# VideoSignal.net
KiCad netlist of a schematic drawn in Altium Designer
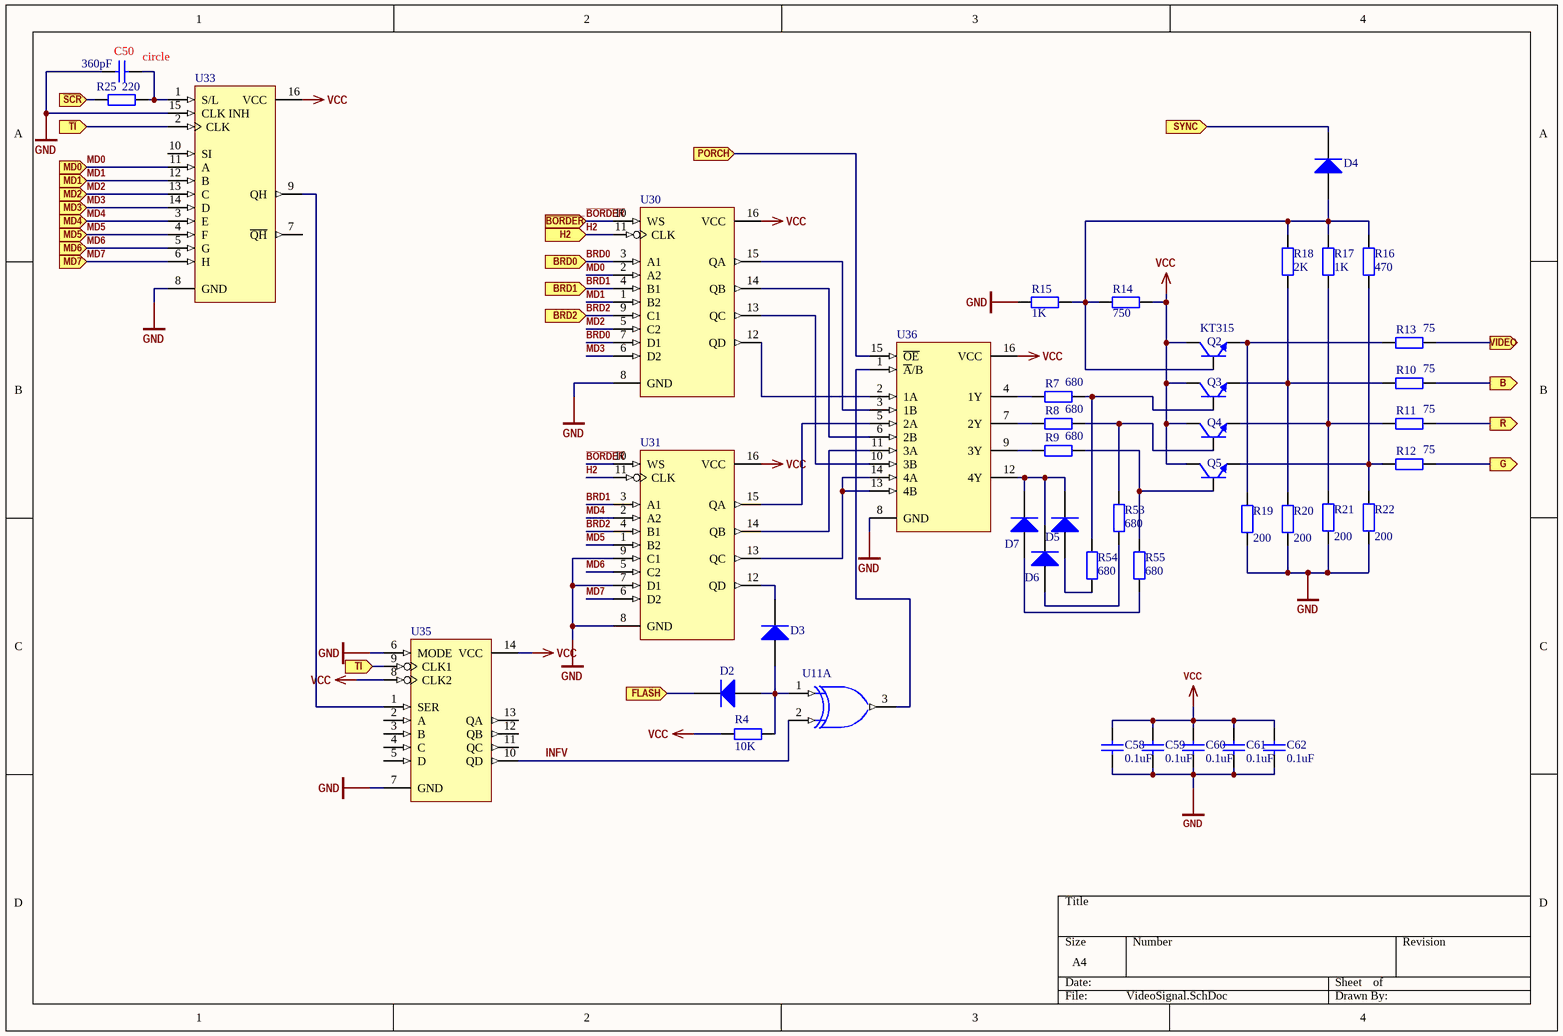
[diagram p0: VideoSignal.SchDoc]

(export (version "E")
  (design (tool "Eeschema 10.0.6"))
  (components
    (comp (ref "C50")
      (value "circle")
      (footprint "RAD-0.3")
      (description "Capacitor")
      (fields (field (name "ALTIUM_VALUE") "360pF") (field (name "PUBLISHER") "Altium Limited"))
      (libsource (lib "Lenin") (part "Cap"))
    )
    (comp (ref "C58")
      (value "0.1uF")
      (footprint "RAD-0.3")
      (description "Capacitor")
      (fields (field (name "Comment") "Cap") (field (name "PUBLISHER") "Altium Limited"))
      (libsource (lib "Lenin") (part "Cap"))
    )
    (comp (ref "C59")
      (value "0.1uF")
      (footprint "RAD-0.3")
      (description "Capacitor")
      (fields (field (name "Comment") "Cap") (field (name "PUBLISHER") "Altium Limited"))
      (libsource (lib "Lenin") (part "Cap"))
    )
    (comp (ref "C60")
      (value "0.1uF")
      (footprint "RAD-0.3")
      (description "Capacitor")
      (fields (field (name "Comment") "Cap") (field (name "PUBLISHER") "Altium Limited"))
      (libsource (lib "Lenin") (part "Cap"))
    )
    (comp (ref "C61")
      (value "0.1uF")
      (footprint "RAD-0.3")
      (description "Capacitor")
      (fields (field (name "Comment") "Cap") (field (name "PUBLISHER") "Altium Limited"))
      (libsource (lib "Lenin") (part "Cap"))
    )
    (comp (ref "C62")
      (value "0.1uF")
      (footprint "RAD-0.3")
      (description "Capacitor")
      (fields (field (name "Comment") "Cap") (field (name "PUBLISHER") "Altium Limited"))
      (libsource (lib "Lenin") (part "Cap"))
    )
    (comp (ref "D2")
      (value "~")
      (footprint "DO-35A")
      (description "Computer Diode")
      (fields (field (name "PUBLISHER") "Altium Limited"))
      (libsource (lib "Miscellaneous Devices") (part "Diode 1N4149"))
    )
    (comp (ref "D3")
      (value "~")
      (footprint "DO-35A")
      (description "Computer Diode")
      (fields (field (name "PUBLISHER") "Altium Limited"))
      (libsource (lib "Miscellaneous Devices") (part "Diode 1N4149"))
    )
    (comp (ref "D4")
      (value "Diode 1N4148")
      (footprint "DO-35")
      (description "High Conductance Fast Diode")
      (fields (field (name "PUBLISHER") "Altium Limited"))
      (libsource (lib "Miscellaneous Devices") (part "Diode 1N4148"))
    )
    (comp (ref "D5")
      (value "Diode 1N4148")
      (footprint "DO-35")
      (description "High Conductance Fast Diode")
      (fields (field (name "PUBLISHER") "Altium Limited"))
      (libsource (lib "Miscellaneous Devices") (part "Diode 1N4148"))
    )
    (comp (ref "D6")
      (value "Diode 1N4148")
      (footprint "DO-35")
      (description "High Conductance Fast Diode")
      (fields (field (name "PUBLISHER") "Altium Limited"))
      (libsource (lib "Miscellaneous Devices") (part "Diode 1N4148"))
    )
    (comp (ref "D7")
      (value "Diode 1N4148")
      (footprint "DO-35")
      (description "High Conductance Fast Diode")
      (fields (field (name "PUBLISHER") "Altium Limited"))
      (libsource (lib "Miscellaneous Devices") (part "Diode 1N4148"))
    )
    (comp (ref "Q2")
      (value "KT315")
      (footprint "Lenin:D35")
      (description "NPN General Purpose Amplifier")
      (fields (field (name "PUBLISHER") "Altium Limited"))
      (libsource (lib "Lenin") (part "KT315"))
    )
    (comp (ref "Q3")
      (value "KT315")
      (footprint "Lenin:D35")
      (description "NPN General Purpose Amplifier")
      (fields (field (name "PUBLISHER") "Altium Limited"))
      (libsource (lib "Lenin") (part "KT315"))
    )
    (comp (ref "Q4")
      (value "KT315")
      (footprint "Lenin:D35")
      (description "NPN General Purpose Amplifier")
      (fields (field (name "PUBLISHER") "Altium Limited"))
      (libsource (lib "Lenin") (part "KT315"))
    )
    (comp (ref "Q5")
      (value "KT315")
      (footprint "Lenin:D35")
      (description "NPN General Purpose Amplifier")
      (fields (field (name "PUBLISHER") "Altium Limited"))
      (libsource (lib "Lenin") (part "KT315"))
    )
    (comp (ref "R4")
      (value "10K")
      (footprint "Lenin:AXIAL-0.4")
      (description "Resistor")
      (fields (field (name "PUBLISHER") "Altium Limited"))
      (libsource (lib "Lenin") (part "Res2"))
    )
    (comp (ref "R7")
      (value "680")
      (footprint "Lenin:AXIAL-0.4")
      (description "Resistor")
      (fields (field (name "PUBLISHER") "Altium Limited"))
      (libsource (lib "Lenin") (part "Res2"))
    )
    (comp (ref "R8")
      (value "680")
      (footprint "Lenin:AXIAL-0.4")
      (description "Resistor")
      (fields (field (name "PUBLISHER") "Altium Limited"))
      (libsource (lib "Lenin") (part "Res2"))
    )
    (comp (ref "R9")
      (value "680")
      (footprint "Lenin:AXIAL-0.4")
      (description "Resistor")
      (fields (field (name "PUBLISHER") "Altium Limited"))
      (libsource (lib "Lenin") (part "Res2"))
    )
    (comp (ref "R10")
      (value "75")
      (footprint "Lenin:AXIAL-0.4")
      (description "Resistor")
      (fields (field (name "PUBLISHER") "Altium Limited"))
      (libsource (lib "Lenin") (part "Res2"))
    )
    (comp (ref "R11")
      (value "75")
      (footprint "Lenin:AXIAL-0.4")
      (description "Resistor")
      (fields (field (name "PUBLISHER") "Altium Limited"))
      (libsource (lib "Lenin") (part "Res2"))
    )
    (comp (ref "R12")
      (value "75")
      (footprint "Lenin:AXIAL-0.4")
      (description "Resistor")
      (fields (field (name "PUBLISHER") "Altium Limited"))
      (libsource (lib "Lenin") (part "Res2"))
    )
    (comp (ref "R13")
      (value "75")
      (footprint "Lenin:AXIAL-0.4")
      (description "Resistor")
      (fields (field (name "PUBLISHER") "Altium Limited"))
      (libsource (lib "Lenin") (part "Res2"))
    )
    (comp (ref "R14")
      (value "750")
      (footprint "Lenin:AXIAL-0.4")
      (description "Resistor")
      (fields (field (name "PUBLISHER") "Altium Limited"))
      (libsource (lib "Lenin") (part "Res2"))
    )
    (comp (ref "R15")
      (value "1K")
      (footprint "Lenin:AXIAL-0.4")
      (description "Resistor")
      (fields (field (name "PUBLISHER") "Altium Limited"))
      (libsource (lib "Lenin") (part "Res2"))
    )
    (comp (ref "R16")
      (value "470")
      (footprint "Lenin:AXIAL-0.4")
      (description "Resistor")
      (fields (field (name "PUBLISHER") "Altium Limited"))
      (libsource (lib "") (part "Res2_1"))
    )
    (comp (ref "R17")
      (value "1K")
      (footprint "Lenin:AXIAL-0.4")
      (description "Resistor")
      (fields (field (name "PUBLISHER") "Altium Limited"))
      (libsource (lib "") (part "Res2_1"))
    )
    (comp (ref "R18")
      (value "2K")
      (footprint "Lenin:AXIAL-0.4")
      (description "Resistor")
      (fields (field (name "PUBLISHER") "Altium Limited"))
      (libsource (lib "") (part "Res2_1"))
    )
    (comp (ref "R19")
      (value "200")
      (footprint "Lenin:AXIAL-0.4")
      (description "Resistor")
      (fields (field (name "PUBLISHER") "Altium Limited"))
      (libsource (lib "") (part "Res2_1"))
    )
    (comp (ref "R20")
      (value "200")
      (footprint "Lenin:AXIAL-0.4")
      (description "Resistor")
      (fields (field (name "PUBLISHER") "Altium Limited"))
      (libsource (lib "") (part "Res2_1"))
    )
    (comp (ref "R21")
      (value "200")
      (footprint "Lenin:AXIAL-0.4")
      (description "Resistor")
      (fields (field (name "PUBLISHER") "Altium Limited"))
      (libsource (lib "") (part "Res2_1"))
    )
    (comp (ref "R22")
      (value "200")
      (footprint "Lenin:AXIAL-0.4")
      (description "Resistor")
      (fields (field (name "PUBLISHER") "Altium Limited"))
      (libsource (lib "") (part "Res2_1"))
    )
    (comp (ref "R25")
      (value "220")
      (footprint "Lenin:AXIAL-0.4")
      (description "Resistor")
      (fields (field (name "PUBLISHER") "Altium Limited"))
      (libsource (lib "") (part "Res2_2"))
    )
    (comp (ref "R53")
      (value "680")
      (footprint "Lenin:AXIAL-0.4")
      (description "Resistor")
      (fields (field (name "Comment") "Res2") (field (name "PUBLISHER") "Altium Limited"))
      (libsource (lib "") (part "Res2_1"))
    )
    (comp (ref "R54")
      (value "680")
      (footprint "Lenin:AXIAL-0.4")
      (description "Resistor")
      (fields (field (name "Comment") "Res2") (field (name "PUBLISHER") "Altium Limited"))
      (libsource (lib "") (part "Res2_1"))
    )
    (comp (ref "R55")
      (value "680")
      (footprint "Lenin:AXIAL-0.4")
      (description "Resistor")
      (fields (field (name "Comment") "Res2") (field (name "PUBLISHER") "Altium Limited"))
      (libsource (lib "") (part "Res2_1"))
    )
    (comp (ref "U11")
      (value "~")
      (footprint "N014")
      (description "Quadruple 2-Input Exclusive-OR Gate")
      (fields (field (name "PUBLISHER") "Altium Limited"))
      (libsource (lib "TI Logic Gate 2") (part "SN74HC86N"))
    )
    (comp (ref "U30")
      (value "~")
      (footprint "N016D")
      (description "Quadruple 2-Input Multiplexer with Storage")
      (fields (field (name "PUBLISHER") "Altium Limited"))
      (libsource (lib "TI Logic Multiplexer") (part "SN74HC298N"))
    )
    (comp (ref "U31")
      (value "~")
      (footprint "N016D")
      (description "Quadruple 2-Input Multiplexer with Storage")
      (fields (field (name "PUBLISHER") "Altium Limited"))
      (libsource (lib "TI Logic Multiplexer") (part "SN74HC298N"))
    )
    (comp (ref "U33")
      (value "~")
      (footprint "N016")
      (description "8-Bit Parallel-Load Shift Register")
      (fields (field (name "PUBLISHER") "Altium Limited"))
      (libsource (lib "TI Logic Register") (part "SN74HC165N"))
    )
    (comp (ref "U35")
      (value "~")
      (footprint "N014")
      (description "4-Bit Parallel-Access Shift Register")
      (fields (field (name "PUBLISHER") "Altium Limited"))
      (libsource (lib "TI Logic Register") (part "SN74LS95BN"))
    )
    (comp (ref "U36")
      (value "~")
      (footprint "N016")
      (description "Quadruple 2-Line to 1-Line Data Selector/Multiplexer with 3-State Outputs")
      (fields (field (name "PUBLISHER") "Altium Limited"))
      (libsource (lib "TI Logic Multiplexer") (part "SN74HC257N"))
    )
  )
  (nets
    (net (code "1") (name "/B") (class "Default")
      (node (ref "R10") (pin "2") (pinfunction "2_2") (pintype "passive"))
    )
    (net (code "2") (name "/BRD0") (class "Default")
      (node (ref "U30") (pin "3") (pinfunction "A1_3") (pintype "input"))
      (node (ref "U30") (pin "7") (pinfunction "D1_7") (pintype "input"))
    )
    (net (code "3") (name "/BRD1") (class "Default")
      (node (ref "U30") (pin "4") (pinfunction "B1_4") (pintype "input"))
      (node (ref "U31") (pin "3") (pinfunction "A1_3") (pintype "input"))
    )
    (net (code "4") (name "/BRD2") (class "Default")
      (node (ref "U30") (pin "9") (pinfunction "C1_9") (pintype "input"))
      (node (ref "U31") (pin "4") (pinfunction "B1_4") (pintype "input"))
    )
    (net (code "5") (name "/FLASH") (class "Default")
      (node (ref "D2") (pin "2") (pinfunction "K_2") (pintype "passive"))
    )
    (net (code "6") (name "/G") (class "Default")
      (node (ref "R12") (pin "2") (pinfunction "2_2") (pintype "passive"))
    )
    (net (code "7") (name "/H2") (class "Default")
      (node (ref "U30") (pin "11") (pinfunction "CLK_11") (pintype "input"))
      (node (ref "U31") (pin "11") (pinfunction "CLK_11") (pintype "input"))
    )
    (net (code "8") (name "/INFV") (class "Default")
      (node (ref "U11") (pin "2") (pinfunction "B_2") (pintype "input"))
      (node (ref "U35") (pin "10") (pinfunction "QD_10") (pintype "output"))
    )
    (net (code "9") (name "/MD0") (class "Default")
      (node (ref "U30") (pin "2") (pinfunction "A2_2") (pintype "input"))
      (node (ref "U33") (pin "11") (pinfunction "A_11") (pintype "input"))
    )
    (net (code "10") (name "/MD1") (class "Default")
      (node (ref "U30") (pin "1") (pinfunction "B2_1") (pintype "input"))
      (node (ref "U33") (pin "12") (pinfunction "B_12") (pintype "input"))
    )
    (net (code "11") (name "/MD2") (class "Default")
      (node (ref "U30") (pin "5") (pinfunction "C2_5") (pintype "input"))
      (node (ref "U33") (pin "13") (pinfunction "C_13") (pintype "input"))
    )
    (net (code "12") (name "/MD3") (class "Default")
      (node (ref "U30") (pin "6") (pinfunction "D2_6") (pintype "input"))
      (node (ref "U33") (pin "14") (pinfunction "D_14") (pintype "input"))
    )
    (net (code "13") (name "/MD4") (class "Default")
      (node (ref "U31") (pin "2") (pinfunction "A2_2") (pintype "input"))
      (node (ref "U33") (pin "3") (pinfunction "E_3") (pintype "input"))
    )
    (net (code "14") (name "/MD5") (class "Default")
      (node (ref "U31") (pin "1") (pinfunction "B2_1") (pintype "input"))
      (node (ref "U33") (pin "4") (pinfunction "F_4") (pintype "input"))
    )
    (net (code "15") (name "/MD6") (class "Default")
      (node (ref "U31") (pin "5") (pinfunction "C2_5") (pintype "input"))
      (node (ref "U33") (pin "5") (pinfunction "G_5") (pintype "input"))
    )
    (net (code "16") (name "/MD7") (class "Default")
      (node (ref "U31") (pin "6") (pinfunction "D2_6") (pintype "input"))
      (node (ref "U33") (pin "6") (pinfunction "H_6") (pintype "input"))
    )
    (net (code "17") (name "/PORCH") (class "Default")
      (node (ref "U36") (pin "15") (pinfunction "~{OE}_15") (pintype "input"))
    )
    (net (code "18") (name "/R") (class "Default")
      (node (ref "R11") (pin "2") (pinfunction "2_2") (pintype "passive"))
    )
    (net (code "19") (name "/SYNC") (class "Default")
      (node (ref "D4") (pin "2") (pinfunction "K_2") (pintype "passive"))
    )
    (net (code "20") (name "/TI") (class "Default")
      (node (ref "U35") (pin "9") (pinfunction "CLK1_9") (pintype "input"))
    )
    (net (code "21") (name "/VIDEO") (class "Default")
      (node (ref "R13") (pin "2") (pinfunction "2_2") (pintype "passive"))
    )
    (net (code "22") (name "/~{BORDER}") (class "Default")
      (node (ref "U30") (pin "10") (pinfunction "WS_10") (pintype "input"))
      (node (ref "U31") (pin "10") (pinfunction "WS_10") (pintype "input"))
    )
    (net (code "23") (name "/~{SCR}") (class "Default")
      (node (ref "R25") (pin "2") (pinfunction "2_2") (pintype "passive"))
    )
    (net (code "24") (name "/~{TI}") (class "Default")
      (node (ref "U33") (pin "2") (pinfunction "CLK_2") (pintype "input"))
    )
    (net (code "25") (name "GND") (class "Default")
      (node (ref "C50") (pin "2") (pinfunction "2_2") (pintype "passive"))
      (node (ref "C58") (pin "1") (pinfunction "1_1") (pintype "passive"))
      (node (ref "C59") (pin "1") (pinfunction "1_1") (pintype "passive"))
      (node (ref "C60") (pin "1") (pinfunction "1_1") (pintype "passive"))
      (node (ref "C61") (pin "1") (pinfunction "1_1") (pintype "passive"))
      (node (ref "C62") (pin "1") (pinfunction "1_1") (pintype "passive"))
      (node (ref "R15") (pin "1") (pinfunction "1_1") (pintype "passive"))
      (node (ref "R19") (pin "1") (pinfunction "1_1") (pintype "passive"))
      (node (ref "R20") (pin "1") (pinfunction "1_1") (pintype "passive"))
      (node (ref "R21") (pin "1") (pinfunction "1_1") (pintype "passive"))
      (node (ref "R22") (pin "1") (pinfunction "1_1") (pintype "passive"))
      (node (ref "U11") (pin "7") (pinfunction "GND_7") (pintype "power_in"))
      (node (ref "U30") (pin "8") (pinfunction "GND_8") (pintype "power_in"))
      (node (ref "U31") (pin "7") (pinfunction "D1_7") (pintype "input"))
      (node (ref "U31") (pin "8") (pinfunction "GND_8") (pintype "power_in"))
      (node (ref "U31") (pin "9") (pinfunction "C1_9") (pintype "input"))
      (node (ref "U33") (pin "15") (pinfunction "CLK_INH_15") (pintype "input"))
      (node (ref "U33") (pin "8") (pinfunction "GND_8") (pintype "power_in"))
      (node (ref "U35") (pin "6") (pinfunction "MODE_6") (pintype "input"))
      (node (ref "U35") (pin "7") (pinfunction "GND_7") (pintype "power_in"))
      (node (ref "U36") (pin "8") (pinfunction "GND_8") (pintype "power_in"))
    )
    (net (code "26") (name "Net-(D2-A)") (class "Default")
      (node (ref "D2") (pin "1") (pinfunction "A_1") (pintype "passive"))
      (node (ref "D3") (pin "1") (pinfunction "A_1") (pintype "passive"))
      (node (ref "R4") (pin "2") (pinfunction "2_2") (pintype "passive"))
      (node (ref "U11") (pin "1") (pinfunction "A_1") (pintype "input"))
    )
    (net (code "27") (name "Net-(D3-K)") (class "Default")
      (node (ref "D3") (pin "2") (pinfunction "K_2") (pintype "passive"))
      (node (ref "U31") (pin "12") (pinfunction "QD_12") (pintype "output"))
    )
    (net (code "28") (name "Net-(D4-A)") (class "Default")
      (node (ref "D4") (pin "1") (pinfunction "A_1") (pintype "passive"))
      (node (ref "Q2") (pin "3") (pinfunction "B_3") (pintype "passive"))
      (node (ref "R14") (pin "1") (pinfunction "1_1") (pintype "passive"))
      (node (ref "R15") (pin "2") (pinfunction "2_2") (pintype "passive"))
      (node (ref "R16") (pin "2") (pinfunction "2_2") (pintype "passive"))
      (node (ref "R17") (pin "2") (pinfunction "2_2") (pintype "passive"))
      (node (ref "R18") (pin "2") (pinfunction "2_2") (pintype "passive"))
    )
    (net (code "29") (name "Net-(D5-A)") (class "Default")
      (node (ref "D5") (pin "1") (pinfunction "A_1") (pintype "passive"))
      (node (ref "R54") (pin "1") (pinfunction "1_1") (pintype "passive"))
    )
    (net (code "30") (name "Net-(D5-K)") (class "Default")
      (node (ref "D5") (pin "2") (pinfunction "K_2") (pintype "passive"))
      (node (ref "D6") (pin "2") (pinfunction "K_2") (pintype "passive"))
      (node (ref "D7") (pin "2") (pinfunction "K_2") (pintype "passive"))
      (node (ref "U36") (pin "12") (pinfunction "4Y_12") (pintype "tri_state"))
    )
    (net (code "31") (name "Net-(D6-A)") (class "Default")
      (node (ref "D6") (pin "1") (pinfunction "A_1") (pintype "passive"))
      (node (ref "R53") (pin "1") (pinfunction "1_1") (pintype "passive"))
    )
    (net (code "32") (name "Net-(D7-A)") (class "Default")
      (node (ref "D7") (pin "1") (pinfunction "A_1") (pintype "passive"))
      (node (ref "R55") (pin "1") (pinfunction "1_1") (pintype "passive"))
    )
    (net (code "33") (name "Net-(Q2-E)") (class "Default")
      (node (ref "Q2") (pin "1") (pinfunction "E_1") (pintype "passive"))
      (node (ref "R13") (pin "1") (pinfunction "1_1") (pintype "passive"))
      (node (ref "R19") (pin "2") (pinfunction "2_2") (pintype "passive"))
    )
    (net (code "34") (name "Net-(Q3-B)") (class "Default")
      (node (ref "Q3") (pin "3") (pinfunction "B_3") (pintype "passive"))
      (node (ref "R54") (pin "2") (pinfunction "2_2") (pintype "passive"))
      (node (ref "R7") (pin "2") (pinfunction "2_2") (pintype "passive"))
    )
    (net (code "35") (name "Net-(Q3-E)") (class "Default")
      (node (ref "Q3") (pin "1") (pinfunction "E_1") (pintype "passive"))
      (node (ref "R10") (pin "1") (pinfunction "1_1") (pintype "passive"))
      (node (ref "R18") (pin "1") (pinfunction "1_1") (pintype "passive"))
      (node (ref "R20") (pin "2") (pinfunction "2_2") (pintype "passive"))
    )
    (net (code "36") (name "Net-(Q4-B)") (class "Default")
      (node (ref "Q4") (pin "3") (pinfunction "B_3") (pintype "passive"))
      (node (ref "R53") (pin "2") (pinfunction "2_2") (pintype "passive"))
      (node (ref "R8") (pin "2") (pinfunction "2_2") (pintype "passive"))
    )
    (net (code "37") (name "Net-(Q4-E)") (class "Default")
      (node (ref "Q4") (pin "1") (pinfunction "E_1") (pintype "passive"))
      (node (ref "R11") (pin "1") (pinfunction "1_1") (pintype "passive"))
      (node (ref "R17") (pin "1") (pinfunction "1_1") (pintype "passive"))
      (node (ref "R21") (pin "2") (pinfunction "2_2") (pintype "passive"))
    )
    (net (code "38") (name "Net-(Q5-B)") (class "Default")
      (node (ref "Q5") (pin "3") (pinfunction "B_3") (pintype "passive"))
      (node (ref "R55") (pin "2") (pinfunction "2_2") (pintype "passive"))
      (node (ref "R9") (pin "2") (pinfunction "2_2") (pintype "passive"))
    )
    (net (code "39") (name "Net-(Q5-E)") (class "Default")
      (node (ref "Q5") (pin "1") (pinfunction "E_1") (pintype "passive"))
      (node (ref "R12") (pin "1") (pinfunction "1_1") (pintype "passive"))
      (node (ref "R16") (pin "1") (pinfunction "1_1") (pintype "passive"))
      (node (ref "R22") (pin "2") (pinfunction "2_2") (pintype "passive"))
    )
    (net (code "40") (name "Net-(U11A-Y)") (class "Default")
      (node (ref "U11") (pin "3") (pinfunction "Y_3") (pintype "output"))
      (node (ref "U36") (pin "1") (pinfunction "~{A}/B_1") (pintype "input"))
    )
    (net (code "41") (name "Net-(U30-QA)") (class "Default")
      (node (ref "U30") (pin "15") (pinfunction "QA_15") (pintype "output"))
      (node (ref "U36") (pin "3") (pinfunction "1B_3") (pintype "input"))
    )
    (net (code "42") (name "Net-(U30-QB)") (class "Default")
      (node (ref "U30") (pin "14") (pinfunction "QB_14") (pintype "output"))
      (node (ref "U36") (pin "6") (pinfunction "2B_6") (pintype "input"))
    )
    (net (code "43") (name "Net-(U30-QC)") (class "Default")
      (node (ref "U30") (pin "13") (pinfunction "QC_13") (pintype "output"))
      (node (ref "U36") (pin "10") (pinfunction "3B_10") (pintype "input"))
    )
    (net (code "44") (name "Net-(U30-QD)") (class "Default")
      (node (ref "U30") (pin "12") (pinfunction "QD_12") (pintype "output"))
      (node (ref "U36") (pin "2") (pinfunction "1A_2") (pintype "input"))
    )
    (net (code "45") (name "Net-(U31-QA)") (class "Default")
      (node (ref "U31") (pin "15") (pinfunction "QA_15") (pintype "output"))
      (node (ref "U36") (pin "5") (pinfunction "2A_5") (pintype "input"))
    )
    (net (code "46") (name "Net-(U31-QB)") (class "Default")
      (node (ref "U31") (pin "14") (pinfunction "QB_14") (pintype "output"))
      (node (ref "U36") (pin "11") (pinfunction "3A_11") (pintype "input"))
    )
    (net (code "47") (name "Net-(U31-QC)") (class "Default")
      (node (ref "U31") (pin "13") (pinfunction "QC_13") (pintype "output"))
      (node (ref "U36") (pin "13") (pinfunction "4B_13") (pintype "input"))
      (node (ref "U36") (pin "14") (pinfunction "4A_14") (pintype "input"))
    )
    (net (code "48") (name "Net-(U33-QH)") (class "Default")
      (node (ref "U33") (pin "9") (pinfunction "QH_9") (pintype "output"))
      (node (ref "U35") (pin "1") (pinfunction "SER_1") (pintype "input"))
    )
    (net (code "49") (name "Net-(U33-S{slash}L)") (class "Default")
      (node (ref "C50") (pin "1") (pinfunction "1_1") (pintype "passive"))
      (node (ref "R25") (pin "1") (pinfunction "1_1") (pintype "passive"))
      (node (ref "U33") (pin "1") (pinfunction "S/L_1") (pintype "input"))
    )
    (net (code "50") (name "Net-(U36-1Y)") (class "Default")
      (node (ref "R7") (pin "1") (pinfunction "1_1") (pintype "passive"))
      (node (ref "U36") (pin "4") (pinfunction "1Y_4") (pintype "tri_state"))
    )
    (net (code "51") (name "Net-(U36-2Y)") (class "Default")
      (node (ref "R8") (pin "1") (pinfunction "1_1") (pintype "passive"))
      (node (ref "U36") (pin "7") (pinfunction "2Y_7") (pintype "tri_state"))
    )
    (net (code "52") (name "Net-(U36-3Y)") (class "Default")
      (node (ref "R9") (pin "1") (pinfunction "1_1") (pintype "passive"))
      (node (ref "U36") (pin "9") (pinfunction "3Y_9") (pintype "tri_state"))
    )
    (net (code "53") (name "VCC") (class "Default")
      (node (ref "C58") (pin "2") (pinfunction "2_2") (pintype "passive"))
      (node (ref "C59") (pin "2") (pinfunction "2_2") (pintype "passive"))
      (node (ref "C60") (pin "2") (pinfunction "2_2") (pintype "passive"))
      (node (ref "C61") (pin "2") (pinfunction "2_2") (pintype "passive"))
      (node (ref "C62") (pin "2") (pinfunction "2_2") (pintype "passive"))
      (node (ref "Q2") (pin "2") (pinfunction "C_2") (pintype "passive"))
      (node (ref "Q3") (pin "2") (pinfunction "C_2") (pintype "passive"))
      (node (ref "Q4") (pin "2") (pinfunction "C_2") (pintype "passive"))
      (node (ref "Q5") (pin "2") (pinfunction "C_2") (pintype "passive"))
      (node (ref "R14") (pin "2") (pinfunction "2_2") (pintype "passive"))
      (node (ref "R4") (pin "1") (pinfunction "1_1") (pintype "passive"))
      (node (ref "U11") (pin "14") (pinfunction "VCC_14") (pintype "power_in"))
      (node (ref "U30") (pin "16") (pinfunction "VCC_16") (pintype "power_in"))
      (node (ref "U31") (pin "16") (pinfunction "VCC_16") (pintype "power_in"))
      (node (ref "U33") (pin "16") (pinfunction "VCC_16") (pintype "power_in"))
      (node (ref "U35") (pin "14") (pinfunction "VCC_14") (pintype "power_in"))
      (node (ref "U35") (pin "8") (pinfunction "CLK2_8") (pintype "input"))
      (node (ref "U36") (pin "16") (pinfunction "VCC_16") (pintype "power_in"))
    )
    (net (code "54") (name "unconnected-(U33-SI-Pad10)") (class "Default")
      (node (ref "U33") (pin "10") (pinfunction "SI_10") (pintype "input"))
    )
    (net (code "55") (name "unconnected-(U33-~{QH}-Pad7)") (class "Default")
      (node (ref "U33") (pin "7") (pinfunction "~{QH}_7") (pintype "output"))
    )
    (net (code "56") (name "unconnected-(U35-A-Pad2)") (class "Default")
      (node (ref "U35") (pin "2") (pinfunction "A_2") (pintype "input"))
    )
    (net (code "57") (name "unconnected-(U35-B-Pad3)") (class "Default")
      (node (ref "U35") (pin "3") (pinfunction "B_3") (pintype "input"))
    )
    (net (code "58") (name "unconnected-(U35-C-Pad4)") (class "Default")
      (node (ref "U35") (pin "4") (pinfunction "C_4") (pintype "input"))
    )
    (net (code "59") (name "unconnected-(U35-D-Pad5)") (class "Default")
      (node (ref "U35") (pin "5") (pinfunction "D_5") (pintype "input"))
    )
    (net (code "60") (name "unconnected-(U35-QA-Pad13)") (class "Default")
      (node (ref "U35") (pin "13") (pinfunction "QA_13") (pintype "output"))
    )
    (net (code "61") (name "unconnected-(U35-QB-Pad12)") (class "Default")
      (node (ref "U35") (pin "12") (pinfunction "QB_12") (pintype "output"))
    )
    (net (code "62") (name "unconnected-(U35-QC-Pad11)") (class "Default")
      (node (ref "U35") (pin "11") (pinfunction "QC_11") (pintype "output"))
    )
  )
)
